# DSO_Front.net
KiCad netlist of a schematic drawn in Altium Designer
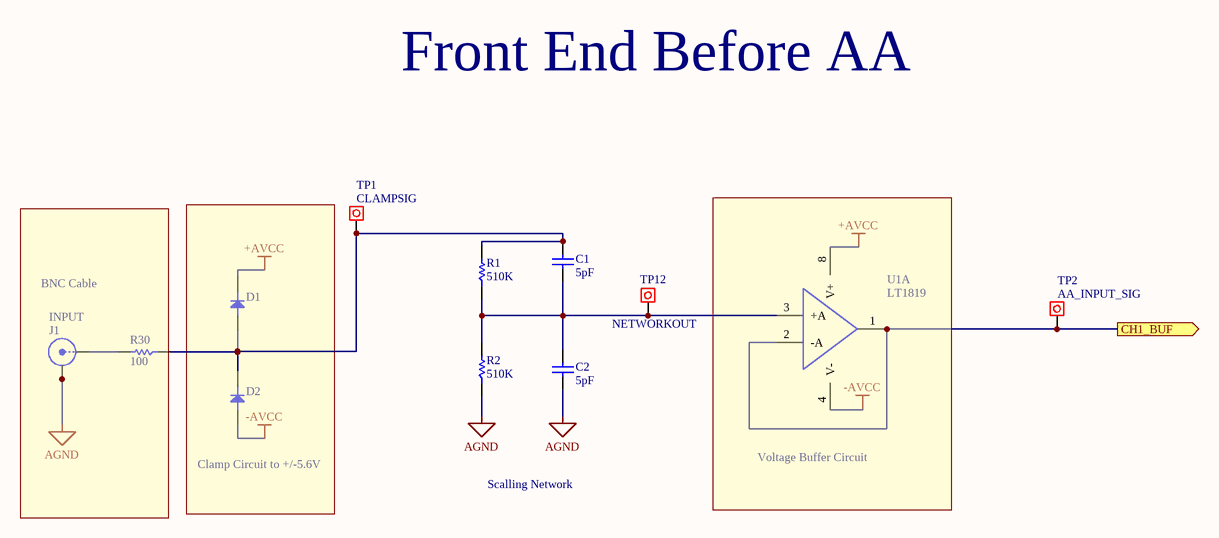
[diagram p0: DSO_Front.SchDoc]

(export (version "E")
  (design (tool "Eeschema 10.0.6"))
  (components
    (comp (ref "C1")
      (value "5pF")
      (footprint "0805C")
      (description "Capacitor")
      (fields (field (name "REVIEWED BY") "RM - 2018/08/05"))
      (libsource (lib "DSO") (part "C"))
    )
    (comp (ref "C2")
      (value "5pF")
      (footprint "0805C")
      (description "Capacitor")
      (fields (field (name "REVIEWED BY") "RM - 2018/08/05"))
      (libsource (lib "DSO") (part "C"))
    )
    (comp (ref "D1")
      (value "Diode")
      (footprint "SOD-123")
      (fields (field (name "REVIEWED BY") "RM - 2018/08/05"))
      (libsource (lib "DSO") (part "D"))
    )
    (comp (ref "D2")
      (value "Diode")
      (footprint "SOD-123")
      (fields (field (name "REVIEWED BY") "RM - 2018/08/05"))
      (libsource (lib "DSO") (part "D"))
    )
    (comp (ref "J1")
      (value "INPUT")
      (footprint "BNC_VERT")
      (description "BNC Straight")
      (fields (field (name "REVIEWED BY") "RM - 2018/08/05"))
      (libsource (lib "DSO") (part "BNC"))
    )
    (comp (ref "R1")
      (value "510K")
      (footprint "0805")
      (description "Resistor")
      (fields (field (name "REVIEWED BY") "RM - 2018/08/05"))
      (libsource (lib "DSO") (part "R"))
    )
    (comp (ref "R2")
      (value "510K")
      (footprint "0805")
      (description "Resistor")
      (fields (field (name "REVIEWED BY") "RM - 2018/08/05"))
      (libsource (lib "DSO") (part "R"))
    )
    (comp (ref "R30")
      (value "100")
      (footprint "0805")
      (description "Resistor")
      (fields (field (name "REVIEWED BY") "RM - 2018/08/05"))
      (libsource (lib "DSO") (part "R"))
    )
    (comp (ref "TP1")
      (value "CLAMPSIG")
      (footprint "Testpoin")
      (description "Pad")
      (fields (field (name "Comment") "INPUT"))
      (libsource (lib "DSO") (part "Test Point"))
    )
    (comp (ref "TP2")
      (value "AA_INPUT_SIG")
      (footprint "Testpoin")
      (description "Pad")
      (fields (field (name "Comment") "INPUT"))
      (libsource (lib "DSO") (part "Test Point"))
    )
    (comp (ref "TP12")
      (value "NETWORKOUT")
      (footprint "Testpoin")
      (description "Pad")
      (fields (field (name "Comment") "INPUT"))
      (libsource (lib "DSO") (part "Test Point"))
    )
    (comp (ref "U1")
      (value "LT1819")
      (footprint "SOIC-8")
      (description "OpAmp High Frequency Dual")
      (fields (field (name "REVIEWED BY") "RM - 2018/08/05"))
      (libsource (lib "DSO") (part "LT1819"))
    )
  )
  (nets
    (net (code "1") (name "+AVCC") (class "Default")
      (node (ref "D1") (pin "K") (pinfunction "K_K") (pintype "passive"))
      (node (ref "U1") (pin "8") (pinfunction "V+_8") (pintype "passive"))
    )
    (net (code "2") (name "-AVCC") (class "Default")
      (node (ref "D2") (pin "A") (pinfunction "A_A") (pintype "passive"))
      (node (ref "U1") (pin "4") (pinfunction "V-_4") (pintype "passive"))
    )
    (net (code "3") (name "/CH1_BUF") (class "Default")
      (node (ref "TP2") (pin "1") (pintype "passive"))
      (node (ref "U1") (pin "1") (pinfunction "OUTA_1") (pintype "passive"))
      (node (ref "U1") (pin "2") (pinfunction "-A_2") (pintype "passive"))
    )
    (net (code "4") (name "AGND") (class "Default")
      (node (ref "C2") (pin "2") (pinfunction "2_2") (pintype "passive"))
      (node (ref "J1") (pin "2") (pinfunction "Y_2") (pintype "passive"))
      (node (ref "J1") (pin "3") (pinfunction "Y_3") (pintype "passive"))
      (node (ref "J1") (pin "4") (pinfunction "Y_4") (pintype "passive"))
      (node (ref "J1") (pin "5") (pinfunction "Y_5") (pintype "passive"))
      (node (ref "R2") (pin "1") (pintype "passive"))
    )
    (net (code "5") (name "Net-(C1-Pad1)") (class "Default")
      (node (ref "C1") (pin "1") (pinfunction "1_1") (pintype "passive"))
      (node (ref "D1") (pin "A") (pinfunction "A_A") (pintype "passive"))
      (node (ref "D2") (pin "K") (pinfunction "K_K") (pintype "passive"))
      (node (ref "R1") (pin "2") (pintype "passive"))
      (node (ref "R30") (pin "1") (pintype "passive"))
      (node (ref "TP1") (pin "1") (pintype "passive"))
    )
    (net (code "6") (name "Net-(J1-X)") (class "Default")
      (node (ref "J1") (pin "1") (pinfunction "X_1") (pintype "passive"))
      (node (ref "R30") (pin "2") (pintype "passive"))
    )
    (net (code "7") (name "Net-(U1A-+A)") (class "Default")
      (node (ref "C1") (pin "2") (pinfunction "2_2") (pintype "passive"))
      (node (ref "C2") (pin "1") (pinfunction "1_1") (pintype "passive"))
      (node (ref "R1") (pin "1") (pintype "passive"))
      (node (ref "R2") (pin "2") (pintype "passive"))
      (node (ref "TP12") (pin "1") (pintype "passive"))
      (node (ref "U1") (pin "3") (pinfunction "+A_3") (pintype "passive"))
    )
  )
)
